# basis.net
KiCad netlist of a schematic drawn in EAGLE
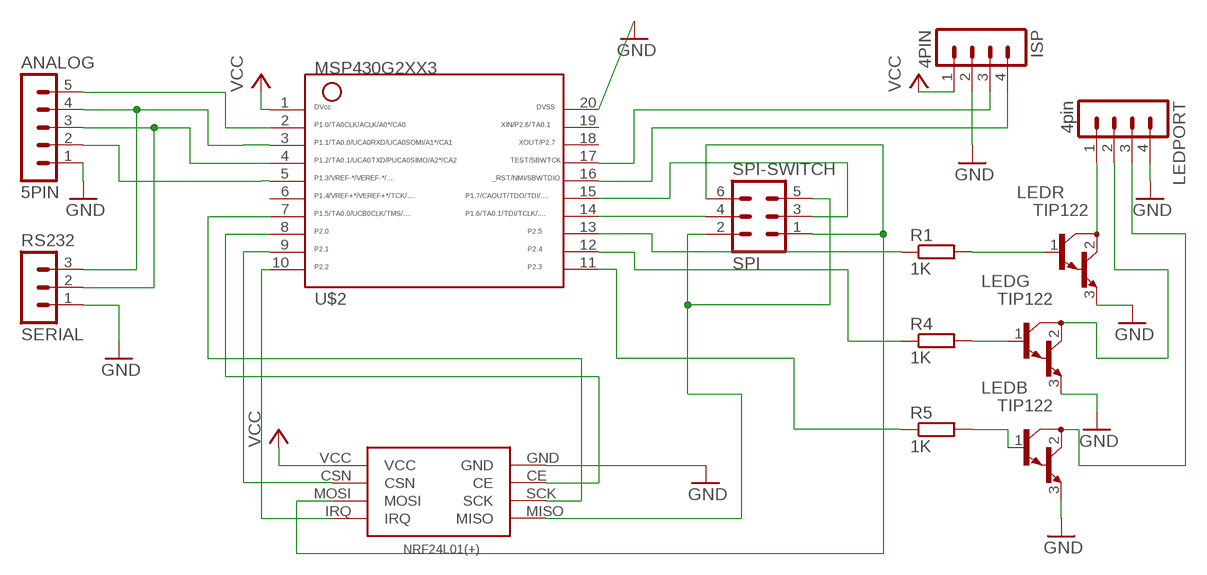
[diagram p0: schematic, sheet 1]

(export (version "E")
  (design (tool "Eeschema 10.0.6"))
  (components
    (comp (ref "ANALOG")
      (value "5PIN")
      (footprint "eagle-import:MA05-1")
      (libsource (lib "eagle-import") (part "MA05-1"))
    )
    (comp (ref "ISP")
      (value "4PIN")
      (footprint "eagle-import:MA04-1")
      (libsource (lib "eagle-import") (part "MA04-1"))
    )
    (comp (ref "LEDB")
      (value "TIP122")
      (footprint "eagle-import:TO220")
      (libsource (lib "eagle-import") (part "TIP122"))
    )
    (comp (ref "LEDG")
      (value "TIP122")
      (footprint "eagle-import:TO220")
      (libsource (lib "eagle-import") (part "TIP122"))
    )
    (comp (ref "LEDPORT")
      (value "4pin")
      (footprint "eagle-import:MA04-1")
      (libsource (lib "eagle-import") (part "MA04-1"))
    )
    (comp (ref "LEDR")
      (value "TIP122")
      (footprint "eagle-import:TO220")
      (libsource (lib "eagle-import") (part "TIP122"))
    )
    (comp (ref "R1")
      (value "1K")
      (footprint "eagle-import:0414_15")
      (libsource (lib "eagle-import") (part "R-EU_0414/15"))
    )
    (comp (ref "R4")
      (value "1K")
      (footprint "eagle-import:0414_15")
      (libsource (lib "eagle-import") (part "R-EU_0414/15"))
    )
    (comp (ref "R5")
      (value "1K")
      (footprint "eagle-import:0414_15")
      (libsource (lib "eagle-import") (part "R-EU_0414/15"))
    )
    (comp (ref "RS232")
      (value "SERIAL")
      (footprint "eagle-import:MA03-1")
      (libsource (lib "eagle-import") (part "MA03-1"))
    )
    (comp (ref "SPI-SWITCH")
      (value "SPI")
      (footprint "eagle-import:MA03-2")
      (libsource (lib "eagle-import") (part "MA03-2"))
    )
    (comp (ref "U$1")
      (value "NFR24L01+-PRINT")
      (footprint "eagle-import:MINI-PCB")
      (libsource (lib "eagle-import") (part "NFR24L01+-PRINT"))
    )
    (comp (ref "U$2")
      (value "G2XX3---N20")
      (footprint "eagle-import:N20")
      (libsource (lib "eagle-import") (part "G2XX3---N20"))
    )
  )
  (nets
    (net (code "1") (name "GND") (class "Default")
      (node (ref "ANALOG") (pin "1") (pinfunction "1_1") (pintype "passive"))
      (node (ref "ISP") (pin "2") (pinfunction "2_2") (pintype "passive"))
      (node (ref "LEDB") (pin "3") (pinfunction "E_3") (pintype "passive"))
      (node (ref "LEDG") (pin "3") (pinfunction "E_3") (pintype "passive"))
      (node (ref "LEDPORT") (pin "4") (pinfunction "4_4") (pintype "passive"))
      (node (ref "LEDR") (pin "3") (pinfunction "E_3") (pintype "passive"))
      (node (ref "RS232") (pin "1") (pinfunction "1_1") (pintype "passive"))
      (node (ref "U$1") (pin "GND") (pinfunction "GND_GND") (pintype "bidirectional"))
      (node (ref "U$2") (pin "20") (pinfunction "20_20") (pintype "bidirectional"))
    )
    (net (code "2") (name "Net-(ANALOG-Pad2)") (class "Default")
      (node (ref "ANALOG") (pin "2") (pinfunction "2_2") (pintype "passive"))
      (node (ref "U$2") (pin "5") (pinfunction "5_5") (pintype "bidirectional"))
    )
    (net (code "3") (name "Net-(ANALOG-Pad3)") (class "Default")
      (node (ref "ANALOG") (pin "3") (pinfunction "3_3") (pintype "passive"))
      (node (ref "RS232") (pin "2") (pinfunction "2_2") (pintype "passive"))
      (node (ref "U$2") (pin "4") (pinfunction "4_4") (pintype "bidirectional"))
    )
    (net (code "4") (name "Net-(ANALOG-Pad4)") (class "Default")
      (node (ref "ANALOG") (pin "4") (pinfunction "4_4") (pintype "passive"))
      (node (ref "RS232") (pin "3") (pinfunction "3_3") (pintype "passive"))
      (node (ref "U$2") (pin "3") (pinfunction "3_3") (pintype "bidirectional"))
    )
    (net (code "5") (name "Net-(ANALOG-Pad5)") (class "Default")
      (node (ref "ANALOG") (pin "5") (pinfunction "5_5") (pintype "passive"))
      (node (ref "U$2") (pin "2") (pinfunction "2_2") (pintype "bidirectional"))
    )
    (net (code "6") (name "Net-(ISP-Pad3)") (class "Default")
      (node (ref "ISP") (pin "3") (pinfunction "3_3") (pintype "passive"))
      (node (ref "U$2") (pin "17") (pinfunction "17_17") (pintype "bidirectional"))
    )
    (net (code "7") (name "Net-(ISP-Pad4)") (class "Default")
      (node (ref "ISP") (pin "4") (pinfunction "4_4") (pintype "passive"))
      (node (ref "U$2") (pin "16") (pinfunction "16_16") (pintype "bidirectional"))
    )
    (net (code "8") (name "Net-(LEDB-B)") (class "Default")
      (node (ref "LEDB") (pin "1") (pinfunction "B_1") (pintype "passive"))
      (node (ref "R5") (pin "2") (pinfunction "2_2") (pintype "passive"))
    )
    (net (code "9") (name "Net-(LEDB-C)") (class "Default")
      (node (ref "LEDB") (pin "2") (pinfunction "C_2") (pintype "passive"))
      (node (ref "LEDPORT") (pin "3") (pinfunction "3_3") (pintype "passive"))
    )
    (net (code "10") (name "Net-(LEDG-B)") (class "Default")
      (node (ref "LEDG") (pin "1") (pinfunction "B_1") (pintype "passive"))
      (node (ref "R4") (pin "2") (pinfunction "2_2") (pintype "passive"))
    )
    (net (code "11") (name "Net-(LEDG-C)") (class "Default")
      (node (ref "LEDG") (pin "2") (pinfunction "C_2") (pintype "passive"))
      (node (ref "LEDPORT") (pin "2") (pinfunction "2_2") (pintype "passive"))
    )
    (net (code "12") (name "Net-(LEDR-B)") (class "Default")
      (node (ref "LEDR") (pin "1") (pinfunction "B_1") (pintype "passive"))
      (node (ref "R1") (pin "2") (pinfunction "2_2") (pintype "passive"))
    )
    (net (code "13") (name "Net-(LEDR-C)") (class "Default")
      (node (ref "LEDPORT") (pin "1") (pinfunction "1_1") (pintype "passive"))
      (node (ref "LEDR") (pin "2") (pinfunction "C_2") (pintype "passive"))
    )
    (net (code "14") (name "Net-(R1-Pad1)") (class "Default")
      (node (ref "R1") (pin "1") (pinfunction "1_1") (pintype "passive"))
      (node (ref "U$2") (pin "13") (pinfunction "13_13") (pintype "bidirectional"))
    )
    (net (code "15") (name "Net-(R4-Pad1)") (class "Default")
      (node (ref "R4") (pin "1") (pinfunction "1_1") (pintype "passive"))
      (node (ref "U$2") (pin "12") (pinfunction "12_12") (pintype "bidirectional"))
    )
    (net (code "16") (name "Net-(R5-Pad1)") (class "Default")
      (node (ref "R5") (pin "1") (pinfunction "1_1") (pintype "passive"))
      (node (ref "U$2") (pin "11") (pinfunction "11_11") (pintype "bidirectional"))
    )
    (net (code "17") (name "Net-(SPI-SWITCH-Pad1)") (class "Default")
      (node (ref "SPI-SWITCH") (pin "1") (pinfunction "1_1") (pintype "passive"))
      (node (ref "SPI-SWITCH") (pin "6") (pinfunction "6_6") (pintype "passive"))
      (node (ref "U$1") (pin "MOSI") (pinfunction "MOSI_MOSI") (pintype "bidirectional"))
    )
    (net (code "18") (name "Net-(SPI-SWITCH-Pad2)") (class "Default")
      (node (ref "SPI-SWITCH") (pin "2") (pinfunction "2_2") (pintype "passive"))
      (node (ref "SPI-SWITCH") (pin "5") (pinfunction "5_5") (pintype "passive"))
      (node (ref "U$1") (pin "MISO") (pinfunction "MISO_MISO") (pintype "bidirectional"))
    )
    (net (code "19") (name "Net-(SPI-SWITCH-Pad3)") (class "Default")
      (node (ref "SPI-SWITCH") (pin "3") (pinfunction "3_3") (pintype "passive"))
      (node (ref "U$2") (pin "15") (pinfunction "15_15") (pintype "bidirectional"))
    )
    (net (code "20") (name "Net-(SPI-SWITCH-Pad4)") (class "Default")
      (node (ref "SPI-SWITCH") (pin "4") (pinfunction "4_4") (pintype "passive"))
      (node (ref "U$2") (pin "14") (pinfunction "14_14") (pintype "bidirectional"))
    )
    (net (code "21") (name "Net-(U$1-PadCE)") (class "Default")
      (node (ref "U$1") (pin "CE") (pinfunction "CE_CE") (pintype "bidirectional"))
      (node (ref "U$2") (pin "8") (pinfunction "8_8") (pintype "bidirectional"))
    )
    (net (code "22") (name "Net-(U$1-PadCSN)") (class "Default")
      (node (ref "U$1") (pin "CSN") (pinfunction "CSN_CSN") (pintype "bidirectional"))
      (node (ref "U$2") (pin "9") (pinfunction "9_9") (pintype "bidirectional"))
    )
    (net (code "23") (name "Net-(U$1-PadIRQ)") (class "Default")
      (node (ref "U$1") (pin "IRQ") (pinfunction "IRQ_IRQ") (pintype "bidirectional"))
      (node (ref "U$2") (pin "10") (pinfunction "10_10") (pintype "bidirectional"))
    )
    (net (code "24") (name "Net-(U$1-PadSCK)") (class "Default")
      (node (ref "U$1") (pin "SCK") (pinfunction "SCK_SCK") (pintype "bidirectional"))
      (node (ref "U$2") (pin "7") (pinfunction "7_7") (pintype "bidirectional"))
    )
    (net (code "25") (name "VCC") (class "Default")
      (node (ref "ISP") (pin "1") (pinfunction "1_1") (pintype "passive"))
      (node (ref "U$1") (pin "VCC") (pinfunction "VCC_VCC") (pintype "bidirectional"))
      (node (ref "U$2") (pin "1") (pinfunction "1_1") (pintype "bidirectional"))
    )
    (net (code "26") (name "unconnected-(U$2-Pad6)") (class "Default")
      (node (ref "U$2") (pin "6") (pinfunction "6_6") (pintype "bidirectional"))
    )
    (net (code "27") (name "unconnected-(U$2-Pad18)") (class "Default")
      (node (ref "U$2") (pin "18") (pinfunction "18_18") (pintype "bidirectional"))
    )
    (net (code "28") (name "unconnected-(U$2-Pad19)") (class "Default")
      (node (ref "U$2") (pin "19") (pinfunction "19_19") (pintype "bidirectional"))
    )
  )
)
